# Low_Distortion_Oscillator_Notch1.net
KiCad netlist of a schematic drawn in Altium Designer
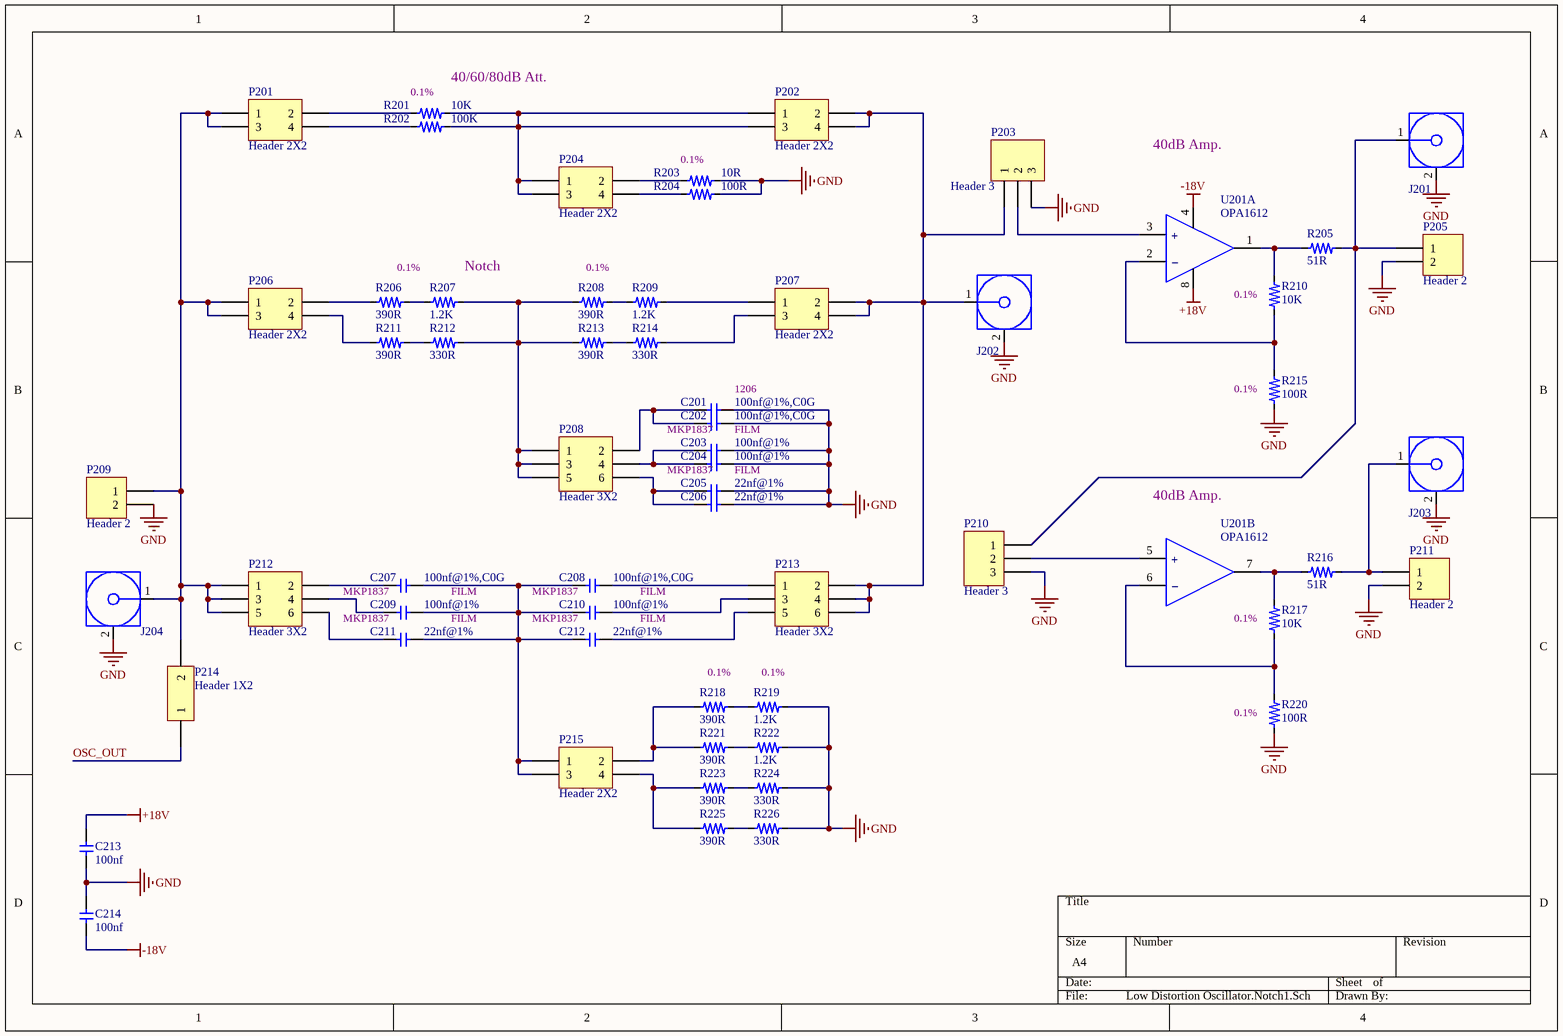
[diagram p0: Low Distortion Oscillator.Notch1.SchDoc]

(export (version "E")
  (design (tool "Eeschema 10.0.6"))
  (components
    (comp (ref "C201")
      (value "100nf@1%,C0G")
      (footprint "C1206")
      (fields (field (name "Comment") "Cap"))
      (libsource (lib "carrot_lib") (part "Cap"))
    )
    (comp (ref "C202")
      (value "100nf@1%,C0G")
      (footprint "C1206")
      (fields (field (name "Comment") "Cap"))
      (libsource (lib "carrot_lib") (part "Cap"))
    )
    (comp (ref "C203")
      (value "100nf@1%")
      (footprint "CAP-FILM-7.2X8.5X10-P5X0.5")
      (fields (field (name "Comment") "Cap-Film"))
      (libsource (lib "carrot_lib") (part "Cap-Film"))
    )
    (comp (ref "C204")
      (value "100nf@1%")
      (footprint "CAP-FILM-7.2X8.5X10-P5X0.5")
      (fields (field (name "Comment") "Cap-Film"))
      (libsource (lib "carrot_lib") (part "Cap-Film"))
    )
    (comp (ref "C205")
      (value "22nf@1%")
      (footprint "CAP-FILM-7.2X5.5X7.0-P5X0.5")
      (fields (field (name "Comment") "Cap-Film"))
      (libsource (lib "carrot_lib") (part "Cap-Film"))
    )
    (comp (ref "C206")
      (value "22nf@1%")
      (footprint "CAP-FILM-7.2X5.5X7.0-P5X0.5")
      (fields (field (name "Comment") "Cap-Film"))
      (libsource (lib "carrot_lib") (part "Cap-Film"))
    )
    (comp (ref "C207")
      (value "100nf@1%,C0G")
      (footprint "C1206")
      (fields (field (name "Comment") "Cap"))
      (libsource (lib "carrot_lib") (part "Cap"))
    )
    (comp (ref "C208")
      (value "100nf@1%,C0G")
      (footprint "C1206")
      (fields (field (name "Comment") "Cap"))
      (libsource (lib "carrot_lib") (part "Cap"))
    )
    (comp (ref "C209")
      (value "100nf@1%")
      (footprint "CAP-FILM-7.2X8.5X10-P5X0.5")
      (fields (field (name "Comment") "Cap-Film"))
      (libsource (lib "carrot_lib") (part "Cap-Film"))
    )
    (comp (ref "C210")
      (value "100nf@1%")
      (footprint "CAP-FILM-7.2X8.5X10-P5X0.5")
      (fields (field (name "Comment") "Cap-Film"))
      (libsource (lib "carrot_lib") (part "Cap-Film"))
    )
    (comp (ref "C211")
      (value "22nf@1%")
      (footprint "CAP-FILM-7.2X5.5X7.0-P5X0.5")
      (fields (field (name "Comment") "Cap-Film"))
      (libsource (lib "carrot_lib") (part "Cap-Film"))
    )
    (comp (ref "C212")
      (value "22nf@1%")
      (footprint "CAP-FILM-7.2X5.5X7.0-P5X0.5")
      (fields (field (name "Comment") "Cap-Film"))
      (libsource (lib "carrot_lib") (part "Cap-Film"))
    )
    (comp (ref "C213")
      (value "100nf")
      (footprint "C0805")
      (fields (field (name "Comment") "Cap"))
      (libsource (lib "carrot_lib") (part "Cap"))
    )
    (comp (ref "C214")
      (value "100nf")
      (footprint "C0805")
      (fields (field (name "Comment") "Cap"))
      (libsource (lib "carrot_lib") (part "Cap"))
    )
    (comp (ref "J201") (value "SMA") (footprint "SMA-2") (libsource (lib "carrot_lib") (part "SMA")))
    (comp (ref "J202") (value "SMA") (footprint "SMA-2") (libsource (lib "carrot_lib") (part "SMA")))
    (comp (ref "J203") (value "SMA") (footprint "SMA-2") (libsource (lib "carrot_lib") (part "SMA")))
    (comp (ref "J204") (value "SMA") (footprint "SMA-2") (libsource (lib "carrot_lib") (part "SMA")))
    (comp (ref "P201")
      (value "Header 2X2")
      (footprint "HDR2X2")
      (description "Header, 2-Pin, Dual row")
      (libsource (lib "carrot_lib") (part "Header 2X2"))
    )
    (comp (ref "P202")
      (value "Header 2X2")
      (footprint "HDR2X2")
      (description "Header, 2-Pin, Dual row")
      (libsource (lib "carrot_lib") (part "Header 2X2"))
    )
    (comp (ref "P203")
      (value "Header 3")
      (footprint "HDR1X3")
      (description "Header, 3-Pin")
      (libsource (lib "") (part "Header 3_1"))
    )
    (comp (ref "P204")
      (value "Header 2X2")
      (footprint "HDR2X2")
      (description "Header, 2-Pin, Dual row")
      (libsource (lib "carrot_lib") (part "Header 2X2"))
    )
    (comp (ref "P205")
      (value "Header 2")
      (footprint "HDR1X2")
      (description "Header, 2-Pin")
      (libsource (lib "") (part "Header 2_1"))
    )
    (comp (ref "P206")
      (value "Header 2X2")
      (footprint "HDR2X2")
      (description "Header, 2-Pin, Dual row")
      (libsource (lib "carrot_lib") (part "Header 2X2"))
    )
    (comp (ref "P207")
      (value "Header 2X2")
      (footprint "HDR2X2")
      (description "Header, 2-Pin, Dual row")
      (libsource (lib "carrot_lib") (part "Header 2X2"))
    )
    (comp (ref "P208")
      (value "Header 3X2")
      (footprint "HDR2X3")
      (description "Header, 3-Pin, Dual row")
      (libsource (lib "carrot_lib") (part "Header 3X2"))
    )
    (comp (ref "P209")
      (value "Header 2")
      (footprint "HDR1X2")
      (description "Header, 2-Pin")
      (libsource (lib "carrot_lib") (part "Header 2"))
    )
    (comp (ref "P210")
      (value "Header 3")
      (footprint "HDR1X3")
      (description "Header, 3-Pin")
      (libsource (lib "carrot_lib") (part "Header 3"))
    )
    (comp (ref "P211")
      (value "Header 2")
      (footprint "HDR1X2")
      (description "Header, 2-Pin")
      (libsource (lib "") (part "Header 2_1"))
    )
    (comp (ref "P212")
      (value "Header 3X2")
      (footprint "HDR2X3")
      (description "Header, 3-Pin, Dual row")
      (libsource (lib "carrot_lib") (part "Header 3X2"))
    )
    (comp (ref "P213")
      (value "Header 3X2")
      (footprint "HDR2X3")
      (description "Header, 3-Pin, Dual row")
      (libsource (lib "carrot_lib") (part "Header 3X2"))
    )
    (comp (ref "P214")
      (value "Header 1X2")
      (footprint "HDR2X1")
      (description "Header, 1-Pin, Dual row")
      (libsource (lib "carrot_lib") (part "Header 1X2"))
    )
    (comp (ref "P215")
      (value "Header 2X2")
      (footprint "HDR2X2")
      (description "Header, 2-Pin, Dual row")
      (libsource (lib "carrot_lib") (part "Header 2X2"))
    )
    (comp (ref "R201")
      (value "10K")
      (footprint "R0805")
      (description "电阻")
      (fields (field (name "Comment") "Res"))
      (libsource (lib "carrot_lib") (part "Res"))
    )
    (comp (ref "R202")
      (value "100K")
      (footprint "R0805")
      (description "电阻")
      (fields (field (name "Comment") "Res"))
      (libsource (lib "carrot_lib") (part "Res"))
    )
    (comp (ref "R203")
      (value "10R")
      (footprint "R0805")
      (description "电阻")
      (fields (field (name "Comment") "Res"))
      (libsource (lib "carrot_lib") (part "Res"))
    )
    (comp (ref "R204")
      (value "100R")
      (footprint "R0805")
      (description "电阻")
      (fields (field (name "Comment") "Res"))
      (libsource (lib "carrot_lib") (part "Res"))
    )
    (comp (ref "R205")
      (value "51R")
      (footprint "R0805")
      (description "电阻")
      (fields (field (name "Comment") "Res"))
      (libsource (lib "carrot_lib") (part "Res"))
    )
    (comp (ref "R206")
      (value "390R")
      (footprint "R0805")
      (description "电阻")
      (fields (field (name "Comment") "Res"))
      (libsource (lib "carrot_lib") (part "Res"))
    )
    (comp (ref "R207")
      (value "1.2K")
      (footprint "R0805")
      (description "电阻")
      (fields (field (name "Comment") "Res"))
      (libsource (lib "carrot_lib") (part "Res"))
    )
    (comp (ref "R208")
      (value "390R")
      (footprint "R0805")
      (description "电阻")
      (fields (field (name "Comment") "Res"))
      (libsource (lib "carrot_lib") (part "Res"))
    )
    (comp (ref "R209")
      (value "1.2K")
      (footprint "R0805")
      (description "电阻")
      (fields (field (name "Comment") "Res"))
      (libsource (lib "carrot_lib") (part "Res"))
    )
    (comp (ref "R210")
      (value "10K")
      (footprint "R0805")
      (description "电阻")
      (fields (field (name "Comment") "Res"))
      (libsource (lib "carrot_lib") (part "Res"))
    )
    (comp (ref "R211")
      (value "390R")
      (footprint "R0805")
      (description "电阻")
      (fields (field (name "Comment") "Res"))
      (libsource (lib "carrot_lib") (part "Res"))
    )
    (comp (ref "R212")
      (value "330R")
      (footprint "R0805")
      (description "电阻")
      (fields (field (name "Comment") "Res"))
      (libsource (lib "carrot_lib") (part "Res"))
    )
    (comp (ref "R213")
      (value "390R")
      (footprint "R0805")
      (description "电阻")
      (fields (field (name "Comment") "Res"))
      (libsource (lib "carrot_lib") (part "Res"))
    )
    (comp (ref "R214")
      (value "330R")
      (footprint "R0805")
      (description "电阻")
      (fields (field (name "Comment") "Res"))
      (libsource (lib "carrot_lib") (part "Res"))
    )
    (comp (ref "R215")
      (value "100R")
      (footprint "R0805")
      (description "电阻")
      (fields (field (name "Comment") "Res"))
      (libsource (lib "carrot_lib") (part "Res"))
    )
    (comp (ref "R216")
      (value "51R")
      (footprint "R0805")
      (description "电阻")
      (fields (field (name "Comment") "Res"))
      (libsource (lib "carrot_lib") (part "Res"))
    )
    (comp (ref "R217")
      (value "10K")
      (footprint "R0805")
      (description "电阻")
      (fields (field (name "Comment") "Res"))
      (libsource (lib "carrot_lib") (part "Res"))
    )
    (comp (ref "R218")
      (value "390R")
      (footprint "R0805")
      (description "电阻")
      (fields (field (name "Comment") "Res"))
      (libsource (lib "carrot_lib") (part "Res"))
    )
    (comp (ref "R219")
      (value "1.2K")
      (footprint "R0805")
      (description "电阻")
      (fields (field (name "Comment") "Res"))
      (libsource (lib "carrot_lib") (part "Res"))
    )
    (comp (ref "R220")
      (value "100R")
      (footprint "R0805")
      (description "电阻")
      (fields (field (name "Comment") "Res"))
      (libsource (lib "carrot_lib") (part "Res"))
    )
    (comp (ref "R221")
      (value "390R")
      (footprint "R0805")
      (description "电阻")
      (fields (field (name "Comment") "Res"))
      (libsource (lib "carrot_lib") (part "Res"))
    )
    (comp (ref "R222")
      (value "1.2K")
      (footprint "R0805")
      (description "电阻")
      (fields (field (name "Comment") "Res"))
      (libsource (lib "carrot_lib") (part "Res"))
    )
    (comp (ref "R223")
      (value "390R")
      (footprint "R0805")
      (description "电阻")
      (fields (field (name "Comment") "Res"))
      (libsource (lib "carrot_lib") (part "Res"))
    )
    (comp (ref "R224")
      (value "330R")
      (footprint "R0805")
      (description "电阻")
      (fields (field (name "Comment") "Res"))
      (libsource (lib "carrot_lib") (part "Res"))
    )
    (comp (ref "R225")
      (value "390R")
      (footprint "R0805")
      (description "电阻")
      (fields (field (name "Comment") "Res"))
      (libsource (lib "carrot_lib") (part "Res"))
    )
    (comp (ref "R226")
      (value "330R")
      (footprint "R0805")
      (description "电阻")
      (fields (field (name "Comment") "Res"))
      (libsource (lib "carrot_lib") (part "Res"))
    )
    (comp (ref "U201")
      (value "OPA1612")
      (footprint "OPA1612-SOIC8")
      (description "OPA161x SoundPlus™ High-Performance, Bipolar-Input Audio Operational Amplifiers")
      (libsource (lib "carrot_lib") (part "OPA1612"))
    )
  )
  (nets
    (net (code "1") (name "+18V") (class "Default")
      (node (ref "C213") (pin "2") (pinfunction "2_2") (pintype "passive"))
      (node (ref "U201") (pin "8") (pinfunction "+Vs_8") (pintype "passive"))
    )
    (net (code "2") (name "-18V") (class "Default")
      (node (ref "C214") (pin "1") (pinfunction "1_1") (pintype "passive"))
      (node (ref "U201") (pin "4") (pinfunction "-Vs_4") (pintype "passive"))
    )
    (net (code "3") (name "/OSC_OUT") (class "Default")
      (node (ref "P214") (pin "1") (pinfunction "1_1") (pintype "passive"))
    )
    (net (code "4") (name "GND") (class "Default")
      (node (ref "C201") (pin "2") (pinfunction "2_2") (pintype "passive"))
      (node (ref "C202") (pin "2") (pinfunction "2_2") (pintype "passive"))
      (node (ref "C203") (pin "2") (pinfunction "2_2") (pintype "passive"))
      (node (ref "C204") (pin "2") (pinfunction "2_2") (pintype "passive"))
      (node (ref "C205") (pin "2") (pinfunction "2_2") (pintype "passive"))
      (node (ref "C206") (pin "2") (pinfunction "2_2") (pintype "passive"))
      (node (ref "C213") (pin "1") (pinfunction "1_1") (pintype "passive"))
      (node (ref "C214") (pin "2") (pinfunction "2_2") (pintype "passive"))
      (node (ref "J201") (pin "2") (pinfunction "GND_2") (pintype "power_in"))
      (node (ref "J202") (pin "2") (pinfunction "GND_2") (pintype "power_in"))
      (node (ref "J203") (pin "2") (pinfunction "GND_2") (pintype "power_in"))
      (node (ref "J204") (pin "2") (pinfunction "GND_2") (pintype "power_in"))
      (node (ref "P203") (pin "3") (pinfunction "3_3") (pintype "passive"))
      (node (ref "P205") (pin "2") (pinfunction "2_2") (pintype "passive"))
      (node (ref "P209") (pin "2") (pinfunction "2_2") (pintype "passive"))
      (node (ref "P210") (pin "3") (pinfunction "3_3") (pintype "passive"))
      (node (ref "P211") (pin "2") (pinfunction "2_2") (pintype "passive"))
      (node (ref "R203") (pin "1") (pinfunction "1_1") (pintype "passive"))
      (node (ref "R204") (pin "1") (pinfunction "1_1") (pintype "passive"))
      (node (ref "R215") (pin "1") (pinfunction "1_1") (pintype "passive"))
      (node (ref "R219") (pin "2") (pinfunction "2_2") (pintype "passive"))
      (node (ref "R220") (pin "1") (pinfunction "1_1") (pintype "passive"))
      (node (ref "R222") (pin "2") (pinfunction "2_2") (pintype "passive"))
      (node (ref "R224") (pin "2") (pinfunction "2_2") (pintype "passive"))
      (node (ref "R226") (pin "2") (pinfunction "2_2") (pintype "passive"))
    )
    (net (code "5") (name "Net-(C201-Pad1)") (class "Default")
      (node (ref "C201") (pin "1") (pinfunction "1_1") (pintype "passive"))
      (node (ref "C202") (pin "1") (pinfunction "1_1") (pintype "passive"))
      (node (ref "P208") (pin "2") (pinfunction "2_2") (pintype "passive"))
    )
    (net (code "6") (name "Net-(C203-Pad1)") (class "Default")
      (node (ref "C203") (pin "1") (pinfunction "1_1") (pintype "passive"))
      (node (ref "C204") (pin "1") (pinfunction "1_1") (pintype "passive"))
      (node (ref "P208") (pin "4") (pinfunction "4_4") (pintype "passive"))
    )
    (net (code "7") (name "Net-(C205-Pad1)") (class "Default")
      (node (ref "C205") (pin "1") (pinfunction "1_1") (pintype "passive"))
      (node (ref "C206") (pin "1") (pinfunction "1_1") (pintype "passive"))
      (node (ref "P208") (pin "6") (pinfunction "6_6") (pintype "passive"))
    )
    (net (code "8") (name "Net-(C207-Pad1)") (class "Default")
      (node (ref "C207") (pin "1") (pinfunction "1_1") (pintype "passive"))
      (node (ref "P212") (pin "2") (pinfunction "2_2") (pintype "passive"))
    )
    (net (code "9") (name "Net-(C207-Pad2)") (class "Default")
      (node (ref "C207") (pin "2") (pinfunction "2_2") (pintype "passive"))
      (node (ref "C208") (pin "1") (pinfunction "1_1") (pintype "passive"))
      (node (ref "C209") (pin "2") (pinfunction "2_2") (pintype "passive"))
      (node (ref "C210") (pin "1") (pinfunction "1_1") (pintype "passive"))
      (node (ref "C211") (pin "2") (pinfunction "2_2") (pintype "passive"))
      (node (ref "C212") (pin "1") (pinfunction "1_1") (pintype "passive"))
      (node (ref "P215") (pin "1") (pinfunction "1_1") (pintype "passive"))
      (node (ref "P215") (pin "3") (pinfunction "3_3") (pintype "passive"))
    )
    (net (code "10") (name "Net-(C208-Pad2)") (class "Default")
      (node (ref "C208") (pin "2") (pinfunction "2_2") (pintype "passive"))
      (node (ref "P213") (pin "1") (pinfunction "1_1") (pintype "passive"))
    )
    (net (code "11") (name "Net-(C209-Pad1)") (class "Default")
      (node (ref "C209") (pin "1") (pinfunction "1_1") (pintype "passive"))
      (node (ref "P212") (pin "4") (pinfunction "4_4") (pintype "passive"))
    )
    (net (code "12") (name "Net-(C210-Pad2)") (class "Default")
      (node (ref "C210") (pin "2") (pinfunction "2_2") (pintype "passive"))
      (node (ref "P213") (pin "3") (pinfunction "3_3") (pintype "passive"))
    )
    (net (code "13") (name "Net-(C211-Pad1)") (class "Default")
      (node (ref "C211") (pin "1") (pinfunction "1_1") (pintype "passive"))
      (node (ref "P212") (pin "6") (pinfunction "6_6") (pintype "passive"))
    )
    (net (code "14") (name "Net-(C212-Pad2)") (class "Default")
      (node (ref "C212") (pin "2") (pinfunction "2_2") (pintype "passive"))
      (node (ref "P213") (pin "5") (pinfunction "5_5") (pintype "passive"))
    )
    (net (code "15") (name "Net-(J201-Signal)") (class "Default")
      (node (ref "J201") (pin "1") (pinfunction "Signal_1") (pintype "power_in"))
      (node (ref "P205") (pin "1") (pinfunction "1_1") (pintype "passive"))
      (node (ref "P210") (pin "1") (pinfunction "1_1") (pintype "passive"))
      (node (ref "R205") (pin "2") (pinfunction "2_2") (pintype "passive"))
    )
    (net (code "16") (name "Net-(J202-Signal)") (class "Default")
      (node (ref "J202") (pin "1") (pinfunction "Signal_1") (pintype "power_in"))
      (node (ref "P202") (pin "2") (pinfunction "2_2") (pintype "passive"))
      (node (ref "P202") (pin "4") (pinfunction "4_4") (pintype "passive"))
      (node (ref "P203") (pin "1") (pinfunction "1_1") (pintype "passive"))
      (node (ref "P207") (pin "2") (pinfunction "2_2") (pintype "passive"))
      (node (ref "P207") (pin "4") (pinfunction "4_4") (pintype "passive"))
      (node (ref "P213") (pin "2") (pinfunction "2_2") (pintype "passive"))
      (node (ref "P213") (pin "4") (pinfunction "4_4") (pintype "passive"))
      (node (ref "P213") (pin "6") (pinfunction "6_6") (pintype "passive"))
    )
    (net (code "17") (name "Net-(J203-Signal)") (class "Default")
      (node (ref "J203") (pin "1") (pinfunction "Signal_1") (pintype "power_in"))
      (node (ref "P211") (pin "1") (pinfunction "1_1") (pintype "passive"))
      (node (ref "R216") (pin "2") (pinfunction "2_2") (pintype "passive"))
    )
    (net (code "18") (name "Net-(J204-Signal)") (class "Default")
      (node (ref "J204") (pin "1") (pinfunction "Signal_1") (pintype "power_in"))
      (node (ref "P201") (pin "1") (pinfunction "1_1") (pintype "passive"))
      (node (ref "P201") (pin "3") (pinfunction "3_3") (pintype "passive"))
      (node (ref "P206") (pin "1") (pinfunction "1_1") (pintype "passive"))
      (node (ref "P206") (pin "3") (pinfunction "3_3") (pintype "passive"))
      (node (ref "P209") (pin "1") (pinfunction "1_1") (pintype "passive"))
      (node (ref "P212") (pin "1") (pinfunction "1_1") (pintype "passive"))
      (node (ref "P212") (pin "3") (pinfunction "3_3") (pintype "passive"))
      (node (ref "P212") (pin "5") (pinfunction "5_5") (pintype "passive"))
      (node (ref "P214") (pin "2") (pinfunction "2_2") (pintype "passive"))
    )
    (net (code "19") (name "Net-(P201-Pad2)") (class "Default")
      (node (ref "P201") (pin "2") (pinfunction "2_2") (pintype "passive"))
      (node (ref "R201") (pin "1") (pinfunction "1_1") (pintype "passive"))
    )
    (net (code "20") (name "Net-(P201-Pad4)") (class "Default")
      (node (ref "P201") (pin "4") (pinfunction "4_4") (pintype "passive"))
      (node (ref "R202") (pin "1") (pinfunction "1_1") (pintype "passive"))
    )
    (net (code "21") (name "Net-(P202-Pad1)") (class "Default")
      (node (ref "P202") (pin "1") (pinfunction "1_1") (pintype "passive"))
      (node (ref "P202") (pin "3") (pinfunction "3_3") (pintype "passive"))
      (node (ref "P204") (pin "1") (pinfunction "1_1") (pintype "passive"))
      (node (ref "P204") (pin "3") (pinfunction "3_3") (pintype "passive"))
      (node (ref "R201") (pin "2") (pinfunction "2_2") (pintype "passive"))
      (node (ref "R202") (pin "2") (pinfunction "2_2") (pintype "passive"))
    )
    (net (code "22") (name "Net-(P204-Pad2)") (class "Default")
      (node (ref "P204") (pin "2") (pinfunction "2_2") (pintype "passive"))
      (node (ref "R203") (pin "2") (pinfunction "2_2") (pintype "passive"))
    )
    (net (code "23") (name "Net-(P204-Pad4)") (class "Default")
      (node (ref "P204") (pin "4") (pinfunction "4_4") (pintype "passive"))
      (node (ref "R204") (pin "2") (pinfunction "2_2") (pintype "passive"))
    )
    (net (code "24") (name "Net-(P206-Pad2)") (class "Default")
      (node (ref "P206") (pin "2") (pinfunction "2_2") (pintype "passive"))
      (node (ref "R206") (pin "1") (pinfunction "1_1") (pintype "passive"))
    )
    (net (code "25") (name "Net-(P206-Pad4)") (class "Default")
      (node (ref "P206") (pin "4") (pinfunction "4_4") (pintype "passive"))
      (node (ref "R211") (pin "1") (pinfunction "1_1") (pintype "passive"))
    )
    (net (code "26") (name "Net-(P207-Pad1)") (class "Default")
      (node (ref "P207") (pin "1") (pinfunction "1_1") (pintype "passive"))
      (node (ref "R209") (pin "2") (pinfunction "2_2") (pintype "passive"))
    )
    (net (code "27") (name "Net-(P207-Pad3)") (class "Default")
      (node (ref "P207") (pin "3") (pinfunction "3_3") (pintype "passive"))
      (node (ref "R214") (pin "2") (pinfunction "2_2") (pintype "passive"))
    )
    (net (code "28") (name "Net-(P208-Pad1)") (class "Default")
      (node (ref "P208") (pin "1") (pinfunction "1_1") (pintype "passive"))
      (node (ref "P208") (pin "3") (pinfunction "3_3") (pintype "passive"))
      (node (ref "P208") (pin "5") (pinfunction "5_5") (pintype "passive"))
      (node (ref "R207") (pin "2") (pinfunction "2_2") (pintype "passive"))
      (node (ref "R208") (pin "1") (pinfunction "1_1") (pintype "passive"))
      (node (ref "R212") (pin "2") (pinfunction "2_2") (pintype "passive"))
      (node (ref "R213") (pin "1") (pinfunction "1_1") (pintype "passive"))
    )
    (net (code "29") (name "Net-(P215-Pad2)") (class "Default")
      (node (ref "P215") (pin "2") (pinfunction "2_2") (pintype "passive"))
      (node (ref "R218") (pin "1") (pinfunction "1_1") (pintype "passive"))
      (node (ref "R221") (pin "1") (pinfunction "1_1") (pintype "passive"))
    )
    (net (code "30") (name "Net-(P215-Pad4)") (class "Default")
      (node (ref "P215") (pin "4") (pinfunction "4_4") (pintype "passive"))
      (node (ref "R223") (pin "1") (pinfunction "1_1") (pintype "passive"))
      (node (ref "R225") (pin "1") (pinfunction "1_1") (pintype "passive"))
    )
    (net (code "31") (name "Net-(R206-Pad2)") (class "Default")
      (node (ref "R206") (pin "2") (pinfunction "2_2") (pintype "passive"))
      (node (ref "R207") (pin "1") (pinfunction "1_1") (pintype "passive"))
    )
    (net (code "32") (name "Net-(R208-Pad2)") (class "Default")
      (node (ref "R208") (pin "2") (pinfunction "2_2") (pintype "passive"))
      (node (ref "R209") (pin "1") (pinfunction "1_1") (pintype "passive"))
    )
    (net (code "33") (name "Net-(R211-Pad2)") (class "Default")
      (node (ref "R211") (pin "2") (pinfunction "2_2") (pintype "passive"))
      (node (ref "R212") (pin "1") (pinfunction "1_1") (pintype "passive"))
    )
    (net (code "34") (name "Net-(R213-Pad2)") (class "Default")
      (node (ref "R213") (pin "2") (pinfunction "2_2") (pintype "passive"))
      (node (ref "R214") (pin "1") (pinfunction "1_1") (pintype "passive"))
    )
    (net (code "35") (name "Net-(R218-Pad2)") (class "Default")
      (node (ref "R218") (pin "2") (pinfunction "2_2") (pintype "passive"))
      (node (ref "R219") (pin "1") (pinfunction "1_1") (pintype "passive"))
    )
    (net (code "36") (name "Net-(R221-Pad2)") (class "Default")
      (node (ref "R221") (pin "2") (pinfunction "2_2") (pintype "passive"))
      (node (ref "R222") (pin "1") (pinfunction "1_1") (pintype "passive"))
    )
    (net (code "37") (name "Net-(R223-Pad2)") (class "Default")
      (node (ref "R223") (pin "2") (pinfunction "2_2") (pintype "passive"))
      (node (ref "R224") (pin "1") (pinfunction "1_1") (pintype "passive"))
    )
    (net (code "38") (name "Net-(R225-Pad2)") (class "Default")
      (node (ref "R225") (pin "2") (pinfunction "2_2") (pintype "passive"))
      (node (ref "R226") (pin "1") (pinfunction "1_1") (pintype "passive"))
    )
    (net (code "39") (name "Net-(U201A-+IN_A)") (class "Default")
      (node (ref "P203") (pin "2") (pinfunction "2_2") (pintype "passive"))
      (node (ref "U201") (pin "3") (pinfunction "+IN_A_3") (pintype "passive"))
    )
    (net (code "40") (name "Net-(U201A--IN_A)") (class "Default")
      (node (ref "R210") (pin "1") (pinfunction "1_1") (pintype "passive"))
      (node (ref "R215") (pin "2") (pinfunction "2_2") (pintype "passive"))
      (node (ref "U201") (pin "2") (pinfunction "-IN_A_2") (pintype "passive"))
    )
    (net (code "41") (name "Net-(U201A-OUT_A)") (class "Default")
      (node (ref "R205") (pin "1") (pinfunction "1_1") (pintype "passive"))
      (node (ref "R210") (pin "2") (pinfunction "2_2") (pintype "passive"))
      (node (ref "U201") (pin "1") (pinfunction "OUT_A_1") (pintype "passive"))
    )
    (net (code "42") (name "Net-(U201B-+IN_B)") (class "Default")
      (node (ref "P210") (pin "2") (pinfunction "2_2") (pintype "passive"))
      (node (ref "U201") (pin "5") (pinfunction "+IN_B_5") (pintype "passive"))
    )
    (net (code "43") (name "Net-(U201B--IN_B)") (class "Default")
      (node (ref "R217") (pin "1") (pinfunction "1_1") (pintype "passive"))
      (node (ref "R220") (pin "2") (pinfunction "2_2") (pintype "passive"))
      (node (ref "U201") (pin "6") (pinfunction "-IN_B_6") (pintype "passive"))
    )
    (net (code "44") (name "Net-(U201B-OUT_B)") (class "Default")
      (node (ref "R216") (pin "1") (pinfunction "1_1") (pintype "passive"))
      (node (ref "R217") (pin "2") (pinfunction "2_2") (pintype "passive"))
      (node (ref "U201") (pin "7") (pinfunction "OUT_B_7") (pintype "passive"))
    )
  )
)
